# Pressure_Module_v2_1_jan2024.net
KiCad netlist of a schematic drawn in EAGLE
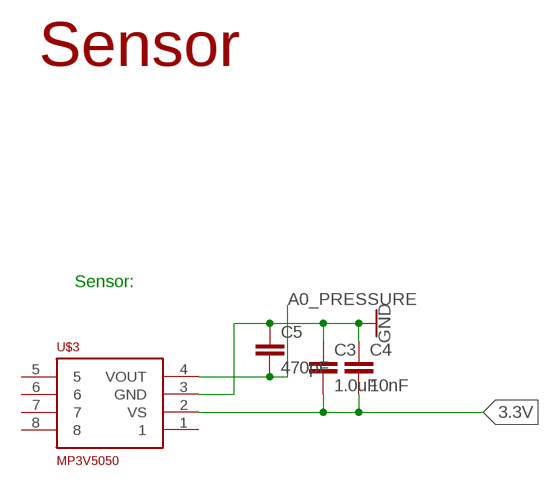
[diagram p0: schematic, sheet 1]
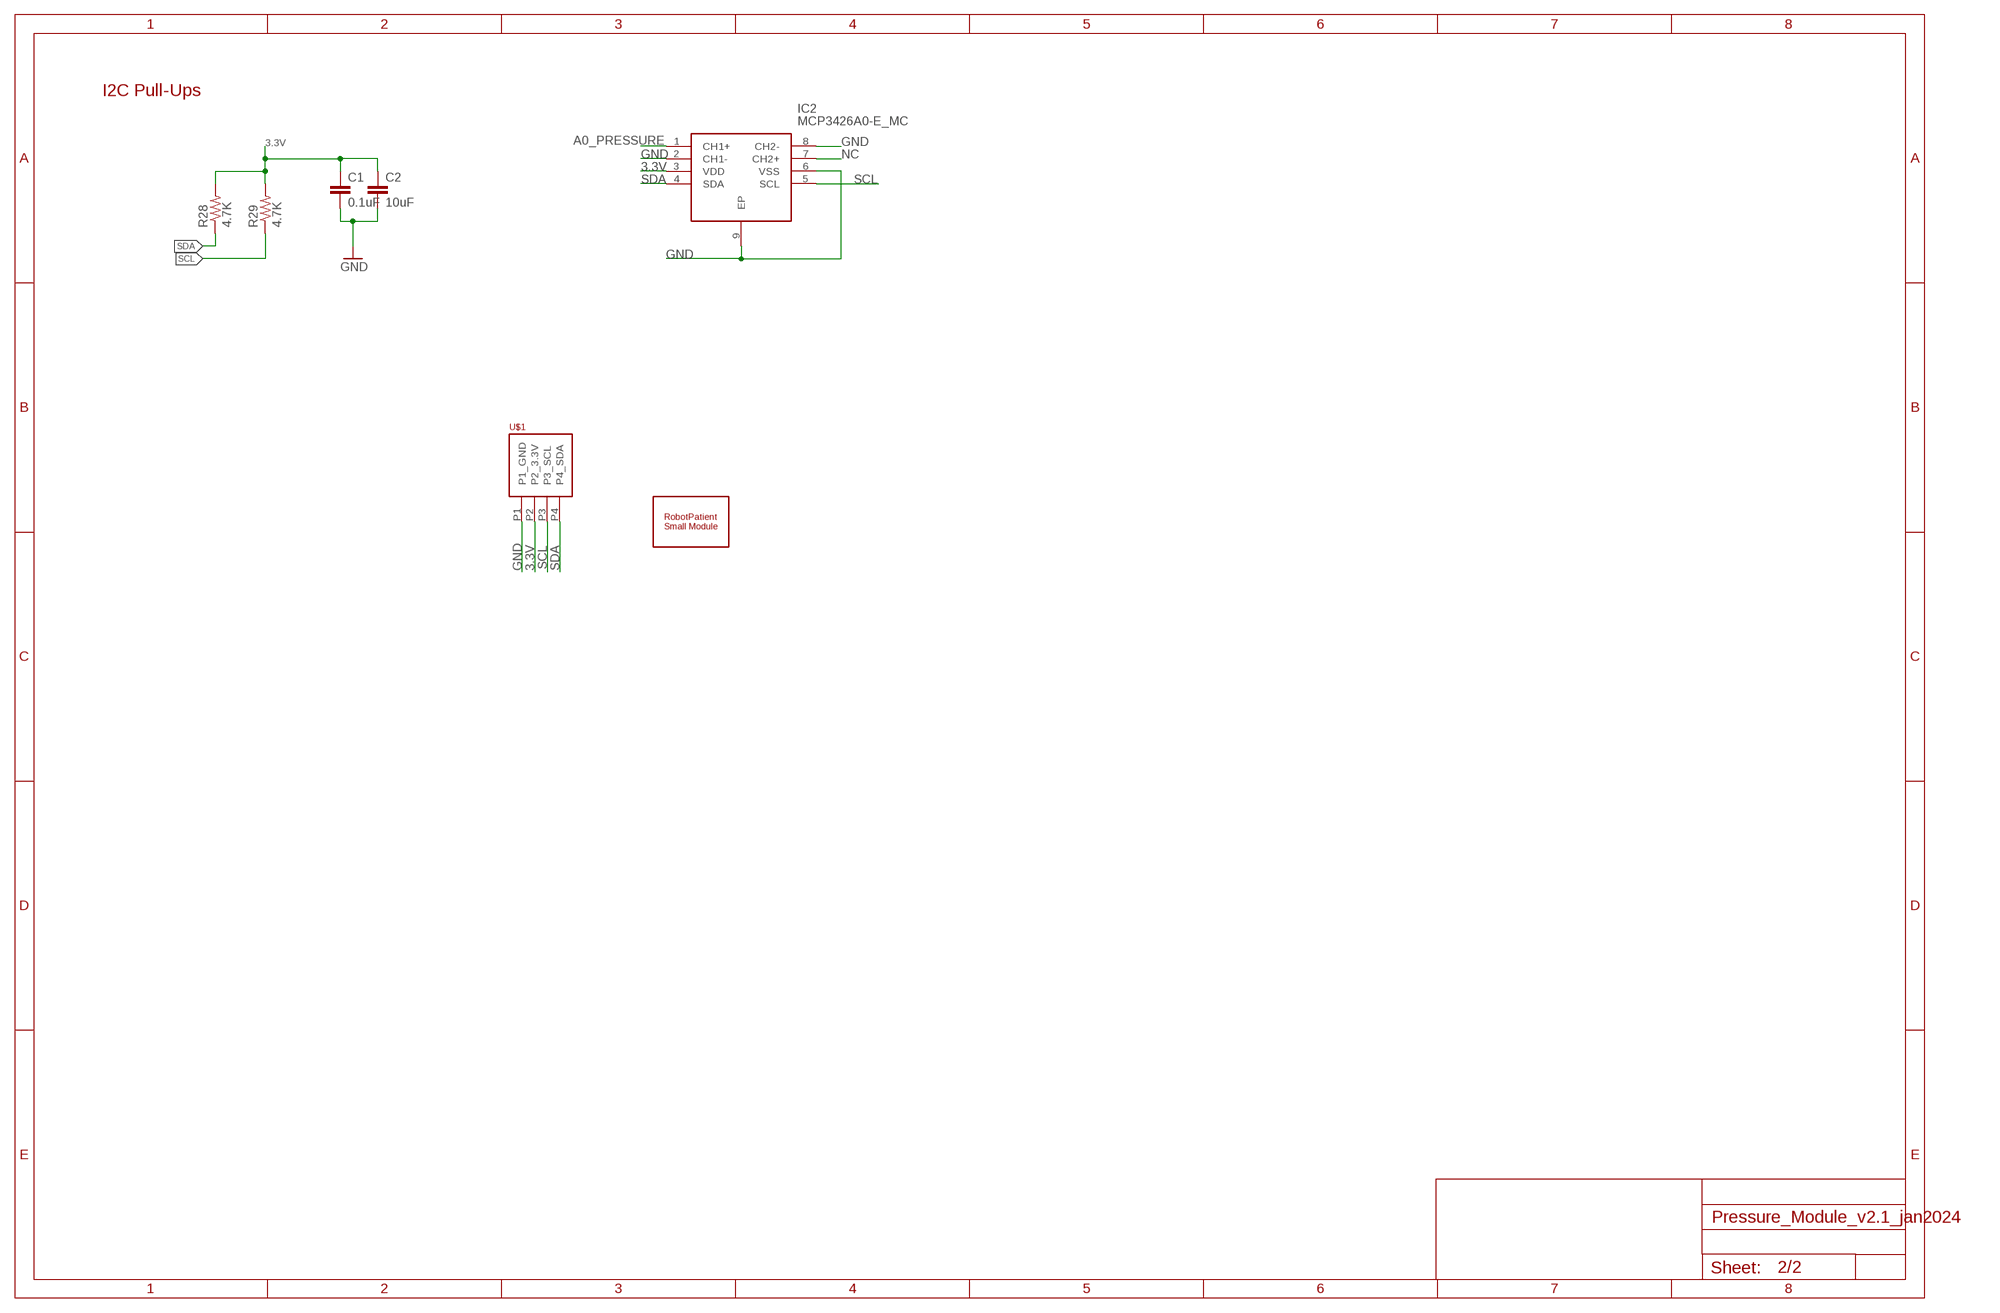
[diagram p1: schematic, sheet 2]

(export (version "E")
  (design (tool "Eeschema 10.0.6"))
  (components
    (comp (ref "C3")
      (value "1.0uF")
      (footprint "eagle-import:0603")
      (libsource (lib "eagle-import") (part "1.0UF-0603-16V-10%"))
    )
    (comp (ref "C4")
      (value "10nF")
      (footprint "eagle-import:0603")
      (libsource (lib "eagle-import") (part "10NF-0603-50V-10%"))
    )
    (comp (ref "C5")
      (value "470pF")
      (footprint "eagle-import:0603")
      (libsource (lib "eagle-import") (part "470PF-0603-50V-5%"))
    )
    (comp (ref "U$3")
      (value "MP3V5050")
      (footprint "eagle-import:PRESSURE_SENSOR")
      (libsource (lib "eagle-import") (part "MP3V5050"))
    )
    (comp (ref "C1")
      (value "0.1uF")
      (footprint "eagle-import:0603")
      (libsource (lib "eagle-import") (part "0.1UF-0603-25V-(+80/-20%)"))
    )
    (comp (ref "C2")
      (value "10uF")
      (footprint "eagle-import:0603")
      (libsource (lib "eagle-import") (part "10UF-0603-6.3V-20%"))
    )
    (comp (ref "IC2")
      (value "MCP3426A0-E_MC")
      (footprint "eagle-import:SON50P300X200X100-9N")
      (fields
        (field (name "MANUFACTURER_PART_NUMBER") "MCP3426A0-E/MC")
        (field (name "MOUSER_PART_NUMBER") "579-MCP3426A0E/MC")
      )
      (libsource (lib "eagle-import") (part "MCP3426A0-E_MC"))
    )
    (comp (ref "R28")
      (value "4.7K")
      (footprint "eagle-import:0603-RES")
      (libsource (lib "eagle-import") (part "4.7KOHM-1/10W-1%(0603)"))
    )
    (comp (ref "R29")
      (value "4.7K")
      (footprint "eagle-import:0603-RES")
      (libsource (lib "eagle-import") (part "4.7KOHM-1/10W-1%(0603)"))
    )
    (comp (ref "U$1")
      (value "PHOENIX_PTSM_M4_THANGLE")
      (footprint "eagle-import:PTSM_M4_TH")
      (libsource (lib "eagle-import") (part "PHOENIX_PTSM_M4_THANGLE"))
    )
    (comp (ref "U$2")
      (value "ROBOTPATIENT_SMALL_MODULEBOARD")
      (footprint "eagle-import:RP_SMALL_SENSOR_OUTLINE")
      (libsource (lib "eagle-import") (part "ROBOTPATIENT_SMALL_MODULEBOARD"))
    )
  )
  (nets
    (net (code "1") (name "3.3V") (class "Default")
      (node (ref "C1") (pin "1") (pinfunction "1_1") (pintype "passive"))
      (node (ref "C2") (pin "1") (pinfunction "1_1") (pintype "passive"))
      (node (ref "C3") (pin "2") (pinfunction "2_2") (pintype "passive"))
      (node (ref "C4") (pin "2") (pinfunction "2_2") (pintype "passive"))
      (node (ref "IC2") (pin "3") (pinfunction "VDD_3") (pintype "bidirectional"))
      (node (ref "R28") (pin "2") (pinfunction "2_2") (pintype "passive"))
      (node (ref "R29") (pin "2") (pinfunction "2_2") (pintype "passive"))
      (node (ref "U$1") (pin "P2") (pinfunction "P2_3.3V_P2") (pintype "power_in"))
      (node (ref "U$3") (pin "2") (pinfunction "VS_2") (pintype "bidirectional"))
    )
    (net (code "2") (name "A0_PRESSURE") (class "Default")
      (node (ref "C5") (pin "2") (pinfunction "2_2") (pintype "passive"))
      (node (ref "IC2") (pin "1") (pinfunction "CH1+_1") (pintype "bidirectional"))
      (node (ref "U$3") (pin "4") (pinfunction "VOUT_4") (pintype "bidirectional"))
    )
    (net (code "3") (name "GND") (class "Default")
      (node (ref "C1") (pin "2") (pinfunction "2_2") (pintype "passive"))
      (node (ref "C2") (pin "2") (pinfunction "2_2") (pintype "passive"))
      (node (ref "C3") (pin "1") (pinfunction "1_1") (pintype "passive"))
      (node (ref "C4") (pin "1") (pinfunction "1_1") (pintype "passive"))
      (node (ref "C5") (pin "1") (pinfunction "1_1") (pintype "passive"))
      (node (ref "IC2") (pin "2") (pinfunction "CH1-_2") (pintype "bidirectional"))
      (node (ref "IC2") (pin "6") (pinfunction "VSS_6") (pintype "bidirectional"))
      (node (ref "IC2") (pin "8") (pinfunction "CH2-_8") (pintype "bidirectional"))
      (node (ref "IC2") (pin "9") (pinfunction "EP_9") (pintype "bidirectional"))
      (node (ref "U$1") (pin "P1") (pinfunction "P1_GND_P1") (pintype "power_in"))
      (node (ref "U$3") (pin "3") (pinfunction "GND_3") (pintype "bidirectional"))
    )
    (net (code "4") (name "NC") (class "Default")
      (node (ref "IC2") (pin "7") (pinfunction "CH2+_7") (pintype "bidirectional"))
    )
    (net (code "5") (name "SCL") (class "Default")
      (node (ref "IC2") (pin "5") (pinfunction "SCL_5") (pintype "bidirectional"))
      (node (ref "R29") (pin "1") (pinfunction "1_1") (pintype "passive"))
      (node (ref "U$1") (pin "P3") (pinfunction "P3_SCL_P3") (pintype "bidirectional"))
    )
    (net (code "6") (name "SDA") (class "Default")
      (node (ref "IC2") (pin "4") (pinfunction "SDA_4") (pintype "bidirectional"))
      (node (ref "R28") (pin "1") (pinfunction "1_1") (pintype "passive"))
      (node (ref "U$1") (pin "P4") (pinfunction "P4_SDA_P4") (pintype "bidirectional"))
    )
    (net (code "7") (name "unconnected-(U$3-Pad1)") (class "Default")
      (node (ref "U$3") (pin "1") (pinfunction "1_1") (pintype "no_connect"))
    )
    (net (code "8") (name "unconnected-(U$3-Pad5)") (class "Default")
      (node (ref "U$3") (pin "5") (pinfunction "5_5") (pintype "no_connect"))
    )
    (net (code "9") (name "unconnected-(U$3-Pad6)") (class "Default")
      (node (ref "U$3") (pin "6") (pinfunction "6_6") (pintype "no_connect"))
    )
    (net (code "10") (name "unconnected-(U$3-Pad7)") (class "Default")
      (node (ref "U$3") (pin "7") (pinfunction "7_7") (pintype "no_connect"))
    )
    (net (code "11") (name "unconnected-(U$3-Pad8)") (class "Default")
      (node (ref "U$3") (pin "8") (pinfunction "8_8") (pintype "no_connect"))
    )
  )
)
